# MB1183_B.net
KiCad netlist of a schematic drawn in Altium Designer
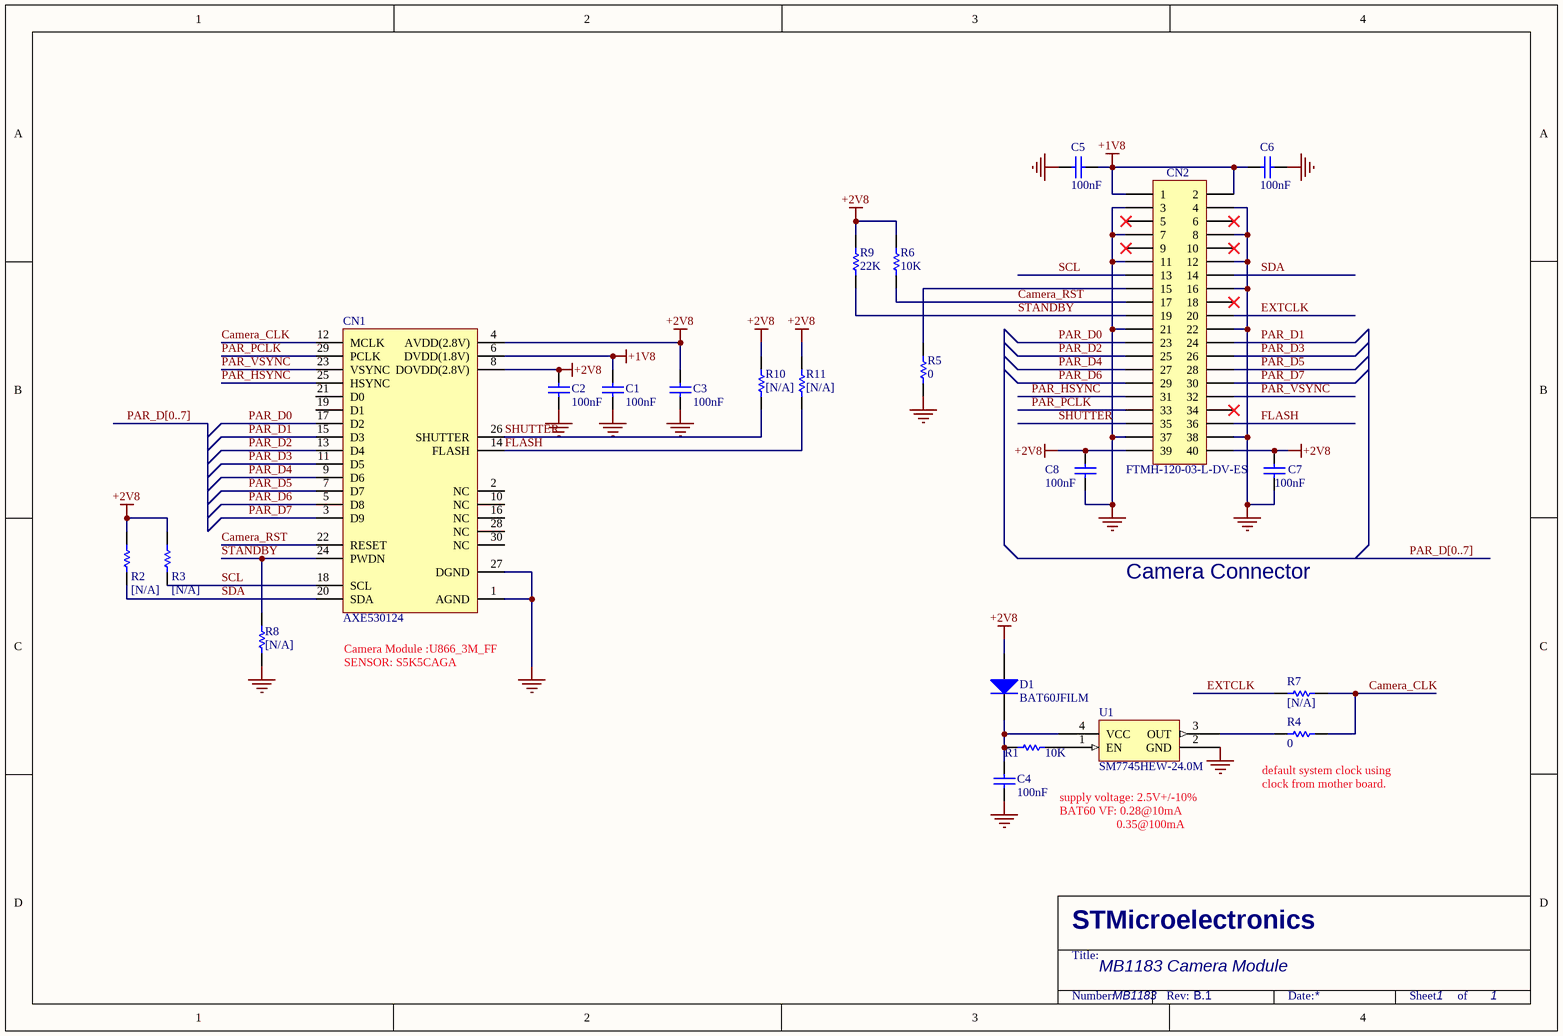
[diagram p0: MB1183_B.SchDoc]

(export (version "E")
  (design (tool "Eeschema 10.0.6"))
  (components
    (comp (ref "C1")
      (value "100nF")
      (footprint "0603C")
      (description "Capacitor")
      (fields (field (name "PUBLISHER") "Altium Limited"))
      (libsource (lib "Miscellaneous Devices") (part "Cap"))
    )
    (comp (ref "C2")
      (value "100nF")
      (footprint "0603C")
      (description "Capacitor")
      (fields (field (name "PUBLISHER") "Altium Limited"))
      (libsource (lib "Miscellaneous Devices") (part "Cap"))
    )
    (comp (ref "C3")
      (value "100nF")
      (footprint "0603C")
      (description "Capacitor")
      (fields (field (name "PUBLISHER") "Altium Limited"))
      (libsource (lib "Miscellaneous Devices") (part "Cap"))
    )
    (comp (ref "C4")
      (value "100nF")
      (footprint "0603C")
      (description "Capacitor")
      (fields (field (name "PUBLISHER") "Altium Limited"))
      (libsource (lib "Miscellaneous Devices") (part "Cap"))
    )
    (comp (ref "C5")
      (value "100nF")
      (footprint "0603C")
      (description "Capacitor")
      (fields (field (name "PUBLISHER") "Altium Limited"))
      (libsource (lib "Miscellaneous Devices") (part "Cap"))
    )
    (comp (ref "C6")
      (value "100nF")
      (footprint "0603C")
      (description "Capacitor")
      (fields (field (name "PUBLISHER") "Altium Limited"))
      (libsource (lib "Miscellaneous Devices") (part "Cap"))
    )
    (comp (ref "C7")
      (value "100nF")
      (footprint "0603C")
      (description "Capacitor")
      (fields (field (name "PUBLISHER") "Altium Limited"))
      (libsource (lib "Miscellaneous Devices") (part "Cap"))
    )
    (comp (ref "C8")
      (value "100nF")
      (footprint "0603C")
      (description "Capacitor")
      (fields (field (name "PUBLISHER") "Altium Limited"))
      (libsource (lib "Miscellaneous Devices") (part "Cap"))
    )
    (comp (ref "CN1")
      (value "AXE530124")
      (footprint "AXE530124")
      (description "CAMERA MODULE")
      (libsource (lib "MB1183") (part "U866_3M_FF"))
    )
    (comp (ref "CN2")
      (value "FTMH-120-03-L-DV-ES")
      (footprint "FTMH-120-03-L-DV-ES")
      (description "20*2Pins, 1mm_SMT, male")
      (fields (field (name "PUBLISHER") "Altium Limited"))
      (libsource (lib "Miscellaneous Connectors") (part "Header 20X2"))
    )
    (comp (ref "D1")
      (value "BAT60JFILM")
      (footprint "SOD-323")
      (description "Default Diode")
      (fields (field (name "PUBLISHER") "Altium Limited"))
      (libsource (lib "Miscellaneous Devices") (part "Diode"))
    )
    (comp (ref "R1")
      (value "10K")
      (footprint "0603R")
      (description "Resistor")
      (fields (field (name "PUBLISHER") "Altium Limited"))
      (libsource (lib "Miscellaneous Devices") (part "Res1"))
    )
    (comp (ref "R2")
      (value "[N/A]")
      (footprint "0603R")
      (description "Resistor 10K")
      (fields (field (name "PUBLISHER") "Altium Limited"))
      (libsource (lib "Miscellaneous Devices") (part "Res1"))
    )
    (comp (ref "R3")
      (value "[N/A]")
      (footprint "0603R")
      (description "Resistor")
      (fields (field (name "PUBLISHER") "Altium Limited"))
      (libsource (lib "Miscellaneous Devices") (part "Res1"))
    )
    (comp (ref "R4")
      (value "0")
      (footprint "0603R")
      (description "Resistor")
      (fields (field (name "PUBLISHER") "Altium Limited"))
      (libsource (lib "Miscellaneous Devices") (part "Res1"))
    )
    (comp (ref "R5")
      (value "0")
      (footprint "0603R")
      (description "Resistor")
      (fields (field (name "PUBLISHER") "Altium Limited"))
      (libsource (lib "Miscellaneous Devices") (part "Res1"))
    )
    (comp (ref "R6")
      (value "10K")
      (footprint "0603R")
      (description "Resistor")
      (fields (field (name "PUBLISHER") "Altium Limited"))
      (libsource (lib "Miscellaneous Devices") (part "Res1"))
    )
    (comp (ref "R7")
      (value "[N/A]")
      (footprint "0603R")
      (description "Resistor")
      (fields (field (name "PUBLISHER") "Altium Limited"))
      (libsource (lib "Miscellaneous Devices") (part "Res1"))
    )
    (comp (ref "R8")
      (value "[N/A]")
      (footprint "0603R")
      (description "Resistor")
      (fields (field (name "PUBLISHER") "Altium Limited"))
      (libsource (lib "Miscellaneous Devices") (part "Res1"))
    )
    (comp (ref "R9")
      (value "22K")
      (footprint "0603R")
      (description "Resistor")
      (fields (field (name "PUBLISHER") "Altium Limited"))
      (libsource (lib "Miscellaneous Devices") (part "Res1"))
    )
    (comp (ref "R10")
      (value "[N/A]")
      (footprint "0603R")
      (description "Resistor")
      (fields (field (name "PUBLISHER") "Altium Limited"))
      (libsource (lib "Miscellaneous Devices") (part "Res1"))
    )
    (comp (ref "R11")
      (value "[N/A]")
      (footprint "0603R")
      (description "Resistor")
      (fields (field (name "PUBLISHER") "Altium Limited"))
      (libsource (lib "Miscellaneous Devices") (part "Res1"))
    )
    (comp (ref "U1")
      (value "SM7745HEW-24.0M")
      (footprint "XTAL_5X7")
      (libsource (lib "MB784") (part "SM7745HEV-50.0M"))
    )
  )
  (nets
    (net (code "1") (name "+1V8") (class "Default")
      (node (ref "C1") (pin "1") (pinfunction "1_1") (pintype "passive"))
      (node (ref "C5") (pin "2") (pinfunction "2_2") (pintype "passive"))
      (node (ref "C6") (pin "1") (pinfunction "1_1") (pintype "passive"))
      (node (ref "CN1") (pin "6") (pinfunction "DVDD(1.8V)_6") (pintype "passive"))
      (node (ref "CN2") (pin "1") (pinfunction "1_1") (pintype "passive"))
      (node (ref "CN2") (pin "2") (pinfunction "2_2") (pintype "passive"))
    )
    (net (code "2") (name "+2V8") (class "Default")
      (node (ref "C2") (pin "1") (pinfunction "1_1") (pintype "passive"))
      (node (ref "C3") (pin "1") (pinfunction "1_1") (pintype "passive"))
      (node (ref "C7") (pin "1") (pinfunction "1_1") (pintype "passive"))
      (node (ref "C8") (pin "1") (pinfunction "1_1") (pintype "passive"))
      (node (ref "CN1") (pin "4") (pinfunction "AVDD(2.8V)_4") (pintype "passive"))
      (node (ref "CN1") (pin "8") (pinfunction "DOVDD(2.8V)_8") (pintype "passive"))
      (node (ref "CN2") (pin "39") (pinfunction "39_39") (pintype "passive"))
      (node (ref "CN2") (pin "40") (pinfunction "40_40") (pintype "passive"))
      (node (ref "D1") (pin "1") (pinfunction "A_1") (pintype "passive"))
      (node (ref "R10") (pin "1") (pinfunction "1_1") (pintype "passive"))
      (node (ref "R11") (pin "1") (pinfunction "1_1") (pintype "passive"))
      (node (ref "R2") (pin "1") (pinfunction "1_1") (pintype "passive"))
      (node (ref "R3") (pin "1") (pinfunction "1_1") (pintype "passive"))
      (node (ref "R6") (pin "1") (pinfunction "1_1") (pintype "passive"))
      (node (ref "R9") (pin "1") (pinfunction "1_1") (pintype "passive"))
    )
    (net (code "3") (name "/Camera_CLK") (class "Default")
      (node (ref "CN1") (pin "12") (pinfunction "MCLK_12") (pintype "passive"))
      (node (ref "R4") (pin "2") (pinfunction "2_2") (pintype "passive"))
      (node (ref "R7") (pin "2") (pinfunction "2_2") (pintype "passive"))
    )
    (net (code "4") (name "/Camera_RST") (class "Default")
      (node (ref "CN1") (pin "22") (pinfunction "RESET_22") (pintype "passive"))
      (node (ref "CN2") (pin "17") (pinfunction "17_17") (pintype "passive"))
      (node (ref "R6") (pin "2") (pinfunction "2_2") (pintype "passive"))
    )
    (net (code "5") (name "/EXTCLK") (class "Default")
      (node (ref "CN2") (pin "20") (pinfunction "20_20") (pintype "passive"))
      (node (ref "R7") (pin "1") (pinfunction "1_1") (pintype "passive"))
    )
    (net (code "6") (name "/FLASH") (class "Default")
      (node (ref "CN1") (pin "14") (pinfunction "FLASH_14") (pintype "passive"))
      (node (ref "CN2") (pin "36") (pinfunction "36_36") (pintype "passive"))
      (node (ref "R11") (pin "2") (pinfunction "2_2") (pintype "passive"))
    )
    (net (code "7") (name "/PAR_D0") (class "Default")
      (node (ref "CN1") (pin "17") (pinfunction "D2_17") (pintype "passive"))
      (node (ref "CN2") (pin "23") (pinfunction "23_23") (pintype "passive"))
    )
    (net (code "8") (name "/PAR_D1") (class "Default")
      (node (ref "CN1") (pin "15") (pinfunction "D3_15") (pintype "passive"))
      (node (ref "CN2") (pin "24") (pinfunction "24_24") (pintype "passive"))
    )
    (net (code "9") (name "/PAR_D2") (class "Default")
      (node (ref "CN1") (pin "13") (pinfunction "D4_13") (pintype "passive"))
      (node (ref "CN2") (pin "25") (pinfunction "25_25") (pintype "passive"))
    )
    (net (code "10") (name "/PAR_D3") (class "Default")
      (node (ref "CN1") (pin "11") (pinfunction "D5_11") (pintype "passive"))
      (node (ref "CN2") (pin "26") (pinfunction "26_26") (pintype "passive"))
    )
    (net (code "11") (name "/PAR_D4") (class "Default")
      (node (ref "CN1") (pin "9") (pinfunction "D6_9") (pintype "passive"))
      (node (ref "CN2") (pin "27") (pinfunction "27_27") (pintype "passive"))
    )
    (net (code "12") (name "/PAR_D5") (class "Default")
      (node (ref "CN1") (pin "7") (pinfunction "D7_7") (pintype "passive"))
      (node (ref "CN2") (pin "28") (pinfunction "28_28") (pintype "passive"))
    )
    (net (code "13") (name "/PAR_D6") (class "Default")
      (node (ref "CN1") (pin "5") (pinfunction "D8_5") (pintype "passive"))
      (node (ref "CN2") (pin "29") (pinfunction "29_29") (pintype "passive"))
    )
    (net (code "14") (name "/PAR_D7") (class "Default")
      (node (ref "CN1") (pin "3") (pinfunction "D9_3") (pintype "passive"))
      (node (ref "CN2") (pin "30") (pinfunction "30_30") (pintype "passive"))
    )
    (net (code "16") (name "/PAR_HSYNC") (class "Default")
      (node (ref "CN1") (pin "25") (pinfunction "HSYNC_25") (pintype "passive"))
      (node (ref "CN2") (pin "31") (pinfunction "31_31") (pintype "passive"))
    )
    (net (code "17") (name "/PAR_PCLK") (class "Default")
      (node (ref "CN1") (pin "29") (pinfunction "PCLK_29") (pintype "passive"))
      (node (ref "CN2") (pin "33") (pinfunction "33_33") (pintype "passive"))
    )
    (net (code "18") (name "/PAR_VSYNC") (class "Default")
      (node (ref "CN1") (pin "23") (pinfunction "VSYNC_23") (pintype "passive"))
      (node (ref "CN2") (pin "32") (pinfunction "32_32") (pintype "passive"))
    )
    (net (code "19") (name "/SCL") (class "Default")
      (node (ref "CN1") (pin "18") (pinfunction "SCL_18") (pintype "passive"))
      (node (ref "CN2") (pin "13") (pinfunction "13_13") (pintype "passive"))
      (node (ref "R3") (pin "2") (pinfunction "2_2") (pintype "passive"))
    )
    (net (code "20") (name "/SDA") (class "Default")
      (node (ref "CN1") (pin "20") (pinfunction "SDA_20") (pintype "passive"))
      (node (ref "CN2") (pin "14") (pinfunction "14_14") (pintype "passive"))
      (node (ref "R2") (pin "2") (pinfunction "2_2") (pintype "passive"))
    )
    (net (code "21") (name "/SHUTTER") (class "Default")
      (node (ref "CN1") (pin "26") (pinfunction "SHUTTER_26") (pintype "passive"))
      (node (ref "CN2") (pin "35") (pinfunction "35_35") (pintype "passive"))
      (node (ref "R10") (pin "2") (pinfunction "2_2") (pintype "passive"))
    )
    (net (code "22") (name "/STANDBY") (class "Default")
      (node (ref "CN1") (pin "24") (pinfunction "PWDN_24") (pintype "passive"))
      (node (ref "CN2") (pin "19") (pinfunction "19_19") (pintype "passive"))
      (node (ref "R8") (pin "2") (pinfunction "2_2") (pintype "passive"))
      (node (ref "R9") (pin "2") (pinfunction "2_2") (pintype "passive"))
    )
    (net (code "23") (name "GND") (class "Default")
      (node (ref "C1") (pin "2") (pinfunction "2_2") (pintype "passive"))
      (node (ref "C2") (pin "2") (pinfunction "2_2") (pintype "passive"))
      (node (ref "C3") (pin "2") (pinfunction "2_2") (pintype "passive"))
      (node (ref "C4") (pin "2") (pinfunction "2_2") (pintype "passive"))
      (node (ref "C5") (pin "1") (pinfunction "1_1") (pintype "passive"))
      (node (ref "C6") (pin "2") (pinfunction "2_2") (pintype "passive"))
      (node (ref "C7") (pin "2") (pinfunction "2_2") (pintype "passive"))
      (node (ref "C8") (pin "2") (pinfunction "2_2") (pintype "passive"))
      (node (ref "CN1") (pin "1") (pinfunction "AGND_1") (pintype "passive"))
      (node (ref "CN1") (pin "27") (pinfunction "DGND_27") (pintype "passive"))
      (node (ref "CN2") (pin "11") (pinfunction "11_11") (pintype "passive"))
      (node (ref "CN2") (pin "12") (pinfunction "12_12") (pintype "passive"))
      (node (ref "CN2") (pin "16") (pinfunction "16_16") (pintype "passive"))
      (node (ref "CN2") (pin "21") (pinfunction "21_21") (pintype "passive"))
      (node (ref "CN2") (pin "22") (pinfunction "22_22") (pintype "passive"))
      (node (ref "CN2") (pin "3") (pinfunction "3_3") (pintype "passive"))
      (node (ref "CN2") (pin "37") (pinfunction "37_37") (pintype "passive"))
      (node (ref "CN2") (pin "38") (pinfunction "38_38") (pintype "passive"))
      (node (ref "CN2") (pin "4") (pinfunction "4_4") (pintype "passive"))
      (node (ref "CN2") (pin "7") (pinfunction "7_7") (pintype "passive"))
      (node (ref "CN2") (pin "8") (pinfunction "8_8") (pintype "passive"))
      (node (ref "R5") (pin "2") (pinfunction "2_2") (pintype "passive"))
      (node (ref "R8") (pin "1") (pinfunction "1_1") (pintype "passive"))
      (node (ref "U1") (pin "2") (pinfunction "GND_2") (pintype "passive"))
    )
    (net (code "24") (name "Net-(CN2-Pad15)") (class "Default")
      (node (ref "CN2") (pin "15") (pinfunction "15_15") (pintype "passive"))
      (node (ref "R5") (pin "1") (pinfunction "1_1") (pintype "passive"))
    )
    (net (code "25") (name "Net-(D1-K)") (class "Default")
      (node (ref "C4") (pin "1") (pinfunction "1_1") (pintype "passive"))
      (node (ref "D1") (pin "2") (pinfunction "K_2") (pintype "passive"))
      (node (ref "R1") (pin "1") (pinfunction "1_1") (pintype "passive"))
      (node (ref "U1") (pin "4") (pinfunction "VCC_4") (pintype "passive"))
    )
    (net (code "26") (name "Net-(U1-EN)") (class "Default")
      (node (ref "R1") (pin "2") (pinfunction "2_2") (pintype "passive"))
      (node (ref "U1") (pin "1") (pinfunction "EN_1") (pintype "input"))
    )
    (net (code "27") (name "Net-(U1-OUT)") (class "Default")
      (node (ref "R4") (pin "1") (pinfunction "1_1") (pintype "passive"))
      (node (ref "U1") (pin "3") (pinfunction "OUT_3") (pintype "output"))
    )
    (net (code "28") (name "unconnected-(CN1-D0-Pad21)") (class "Default")
      (node (ref "CN1") (pin "21") (pinfunction "D0_21") (pintype "passive"))
    )
    (net (code "29") (name "unconnected-(CN1-D1-Pad19)") (class "Default")
      (node (ref "CN1") (pin "19") (pinfunction "D1_19") (pintype "passive"))
    )
    (net (code "30") (name "unconnected-(CN1-NC-Pad2)") (class "Default")
      (node (ref "CN1") (pin "2") (pinfunction "NC_2") (pintype "passive"))
    )
    (net (code "31") (name "unconnected-(CN1-NC-Pad10)") (class "Default")
      (node (ref "CN1") (pin "10") (pinfunction "NC_10") (pintype "passive"))
    )
    (net (code "32") (name "unconnected-(CN1-NC-Pad16)") (class "Default")
      (node (ref "CN1") (pin "16") (pinfunction "NC_16") (pintype "passive"))
    )
    (net (code "33") (name "unconnected-(CN1-NC-Pad28)") (class "Default")
      (node (ref "CN1") (pin "28") (pinfunction "NC_28") (pintype "passive"))
    )
    (net (code "34") (name "unconnected-(CN1-NC-Pad30)") (class "Default")
      (node (ref "CN1") (pin "30") (pinfunction "NC_30") (pintype "passive"))
    )
    (net (code "35") (name "unconnected-(CN2-Pad5)") (class "Default")
      (node (ref "CN2") (pin "5") (pinfunction "5_5") (pintype "passive+no_connect"))
    )
    (net (code "36") (name "unconnected-(CN2-Pad6)") (class "Default")
      (node (ref "CN2") (pin "6") (pinfunction "6_6") (pintype "passive+no_connect"))
    )
    (net (code "37") (name "unconnected-(CN2-Pad9)") (class "Default")
      (node (ref "CN2") (pin "9") (pinfunction "9_9") (pintype "passive+no_connect"))
    )
    (net (code "38") (name "unconnected-(CN2-Pad10)") (class "Default")
      (node (ref "CN2") (pin "10") (pinfunction "10_10") (pintype "passive+no_connect"))
    )
    (net (code "39") (name "unconnected-(CN2-Pad18)") (class "Default")
      (node (ref "CN2") (pin "18") (pinfunction "18_18") (pintype "passive+no_connect"))
    )
    (net (code "40") (name "unconnected-(CN2-Pad34)") (class "Default")
      (node (ref "CN2") (pin "34") (pinfunction "34_34") (pintype "passive+no_connect"))
    )
  )
)
